# board.net
KiCad netlist of a schematic drawn in EAGLE
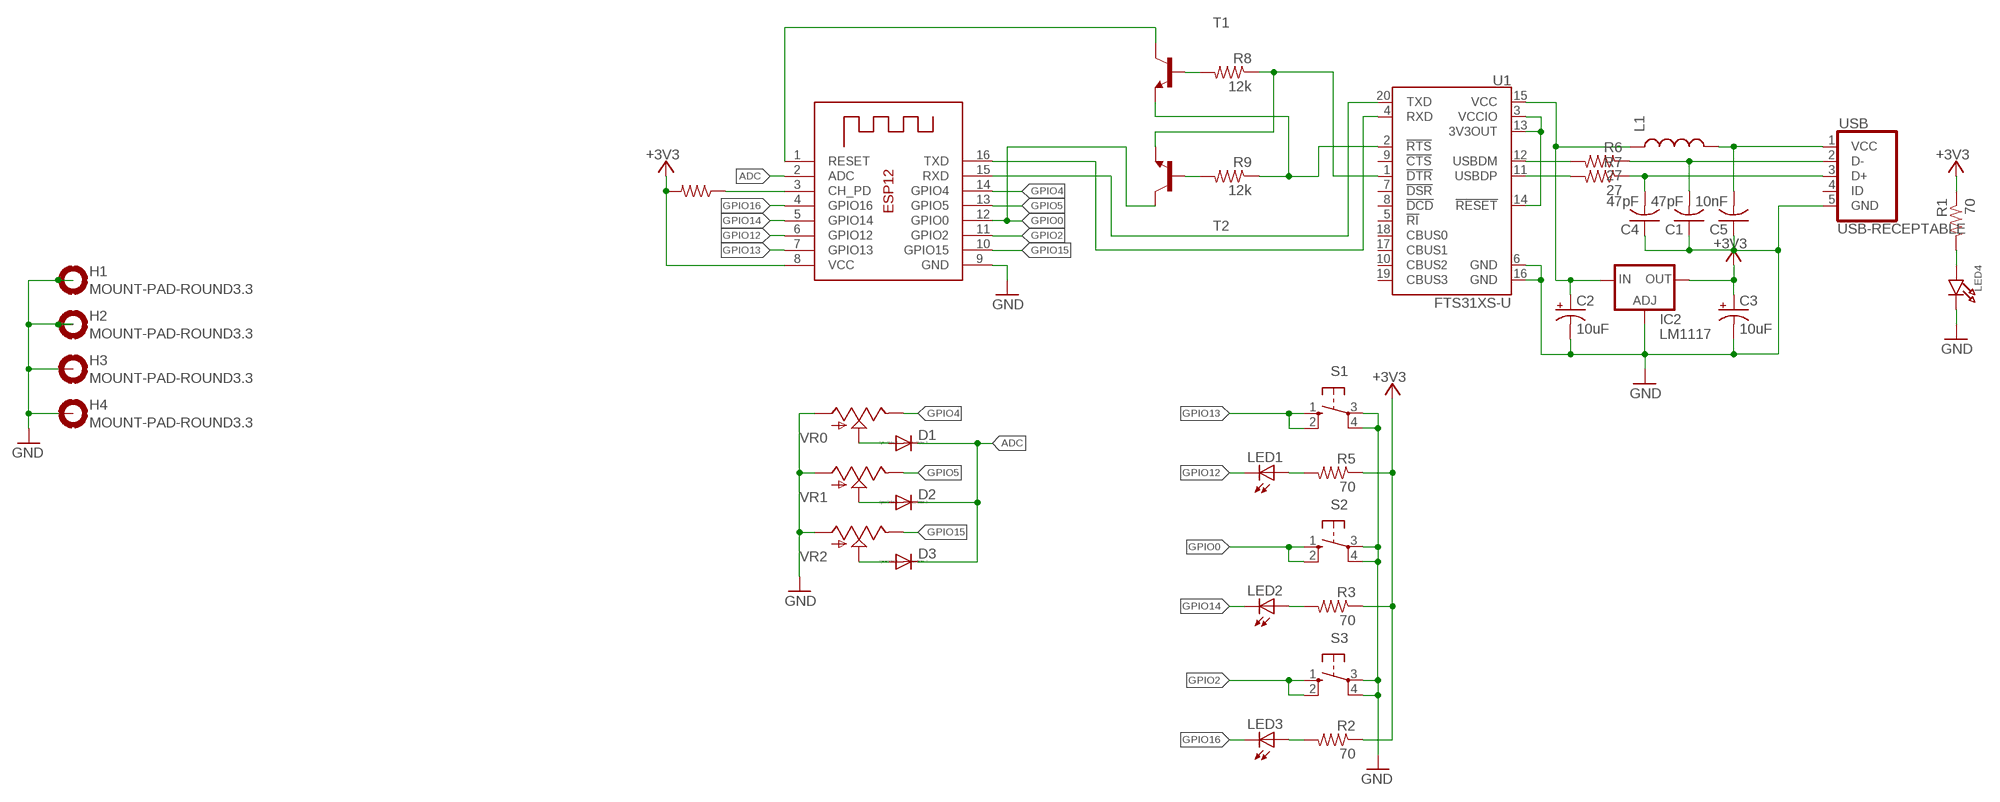
[diagram p0: schematic, sheet 1]

(export (version "E")
  (design (tool "Eeschema 10.0.6"))
  (components
    (comp (ref "C1")
      (value "47pF")
      (footprint "eagle-import:C0603")
      (libsource (lib "eagle-import") (part "C-USC0603"))
    )
    (comp (ref "C2")
      (value "10uF")
      (footprint "eagle-import:153CLV-0405")
      (libsource (lib "eagle-import") (part "CPOL-US153CLV-0405"))
    )
    (comp (ref "C3")
      (value "10uF")
      (footprint "eagle-import:153CLV-0405")
      (libsource (lib "eagle-import") (part "CPOL-US153CLV-0405"))
    )
    (comp (ref "C4")
      (value "47pF")
      (footprint "eagle-import:C0603")
      (libsource (lib "eagle-import") (part "C-USC0603"))
    )
    (comp (ref "C5")
      (value "10nF")
      (footprint "eagle-import:C0603")
      (libsource (lib "eagle-import") (part "C-USC0603"))
    )
    (comp (ref "D1")
      (value "DIODE-DO214AC")
      (footprint "eagle-import:DO214AC")
      (libsource (lib "eagle-import") (part "DIODE-DO214AC"))
    )
    (comp (ref "D2")
      (value "DIODE-DO214AC")
      (footprint "eagle-import:DO214AC")
      (libsource (lib "eagle-import") (part "DIODE-DO214AC"))
    )
    (comp (ref "D3")
      (value "DIODE-DO214AC")
      (footprint "eagle-import:DO214AC")
      (libsource (lib "eagle-import") (part "DIODE-DO214AC"))
    )
    (comp (ref "H1")
      (value "MOUNT-PAD-ROUND3.3")
      (footprint "eagle-import:3,3-PAD")
      (libsource (lib "eagle-import") (part "MOUNT-PAD-ROUND3.3"))
    )
    (comp (ref "H2")
      (value "MOUNT-PAD-ROUND3.3")
      (footprint "eagle-import:3,3-PAD")
      (libsource (lib "eagle-import") (part "MOUNT-PAD-ROUND3.3"))
    )
    (comp (ref "H3")
      (value "MOUNT-PAD-ROUND3.3")
      (footprint "eagle-import:3,3-PAD")
      (libsource (lib "eagle-import") (part "MOUNT-PAD-ROUND3.3"))
    )
    (comp (ref "H4")
      (value "MOUNT-PAD-ROUND3.3")
      (footprint "eagle-import:3,3-PAD")
      (libsource (lib "eagle-import") (part "MOUNT-PAD-ROUND3.3"))
    )
    (comp (ref "IC2")
      (value "LM1117")
      (footprint "eagle-import:DPACK")
      (libsource (lib "eagle-import") (part "LD117A?DT-TR"))
    )
    (comp (ref "L1")
      (value "INDUCTOR0805")
      (footprint "eagle-import:0805")
      (libsource (lib "eagle-import") (part "INDUCTOR0805"))
    )
    (comp (ref "LED1")
      (value "LED3MM")
      (footprint "eagle-import:LED3MM")
      (libsource (lib "eagle-import") (part "LED3MM"))
    )
    (comp (ref "LED2")
      (value "LED3MM")
      (footprint "eagle-import:LED3MM")
      (libsource (lib "eagle-import") (part "LED3MM"))
    )
    (comp (ref "LED3")
      (value "LED3MM")
      (footprint "eagle-import:LED3MM")
      (libsource (lib "eagle-import") (part "LED3MM"))
    )
    (comp (ref "LED4")
      (value "LED0805")
      (footprint "eagle-import:CHIPLED_0805")
      (libsource (lib "eagle-import") (part "LED0805"))
    )
    (comp (ref "R1")
      (value "70")
      (footprint "eagle-import:R0603")
      (libsource (lib "eagle-import") (part "R-US_R0603"))
    )
    (comp (ref "R2")
      (value "70")
      (footprint "eagle-import:R0603")
      (libsource (lib "eagle-import") (part "R-US_R0603"))
    )
    (comp (ref "R3")
      (value "70")
      (footprint "eagle-import:R0603")
      (libsource (lib "eagle-import") (part "R-US_R0603"))
    )
    (comp (ref "R4")
      (value "10k")
      (footprint "eagle-import:R0603")
      (libsource (lib "eagle-import") (part "R-US_R0603"))
    )
    (comp (ref "R5")
      (value "70")
      (footprint "eagle-import:R0603")
      (libsource (lib "eagle-import") (part "R-US_R0603"))
    )
    (comp (ref "R6")
      (value "27")
      (footprint "eagle-import:R0603")
      (libsource (lib "eagle-import") (part "R-US_R0603"))
    )
    (comp (ref "R7")
      (value "27")
      (footprint "eagle-import:R0603")
      (libsource (lib "eagle-import") (part "R-US_R0603"))
    )
    (comp (ref "R8")
      (value "12k")
      (footprint "eagle-import:R0603")
      (libsource (lib "eagle-import") (part "R-US_R0603"))
    )
    (comp (ref "R9")
      (value "12k")
      (footprint "eagle-import:R0603")
      (libsource (lib "eagle-import") (part "R-US_R0603"))
    )
    (comp (ref "S1")
      (value "10-XX")
      (footprint "eagle-import:B3F-10XX")
      (fields (field (name "MPN") "B3F-1000"))
      (libsource (lib "eagle-import") (part "10-XX"))
    )
    (comp (ref "S2")
      (value "10-XX")
      (footprint "eagle-import:B3F-10XX")
      (fields (field (name "MPN") "B3F-1000"))
      (libsource (lib "eagle-import") (part "10-XX"))
    )
    (comp (ref "S3")
      (value "10-XX")
      (footprint "eagle-import:B3F-10XX")
      (fields (field (name "MPN") "B3F-1000"))
      (libsource (lib "eagle-import") (part "10-XX"))
    )
    (comp (ref "T1")
      (value "MMBT918LT1-NPN-SOT23-BEC")
      (footprint "eagle-import:SOT23-BEC")
      (libsource (lib "eagle-import") (part "-NPN-SOT23-BECMMBT918LT1"))
    )
    (comp (ref "T2")
      (value "MMBT918LT1-NPN-SOT23-BEC")
      (footprint "eagle-import:SOT23-BEC")
      (libsource (lib "eagle-import") (part "-NPN-SOT23-BECMMBT918LT1"))
    )
    (comp (ref "U1")
      (value "FTS31XS-U")
      (footprint "eagle-import:SSOP20_L")
      (libsource (lib "eagle-import") (part "FT231XS"))
    )
    (comp (ref "USB")
      (value "USB-RECEPTABLE")
      (footprint "eagle-import:FCI-10103594-0001LF")
      (libsource (lib "eagle-import") (part "USB-RECEPTABLE"))
    )
    (comp (ref "VR0")
      (value "SLIDERPTA3043")
      (footprint "eagle-import:PTA3043-2015CPB103")
      (libsource (lib "eagle-import") (part "SLIDERPTA3043"))
    )
    (comp (ref "VR1")
      (value "SLIDERPTA3043")
      (footprint "eagle-import:PTA3043-2015CPB103")
      (libsource (lib "eagle-import") (part "SLIDERPTA3043"))
    )
    (comp (ref "VR2")
      (value "SLIDERPTA3043")
      (footprint "eagle-import:PTA3043-2015CPB103")
      (libsource (lib "eagle-import") (part "SLIDERPTA3043"))
    )
    (comp (ref "X1")
      (value "ESP-12")
      (footprint "eagle-import:ESP-12")
      (libsource (lib "eagle-import") (part "ESP-12"))
    )
  )
  (nets
    (net (code "1") (name "+3V3") (class "Default")
      (node (ref "C3") (pin "+") (pinfunction "+_+") (pintype "passive"))
      (node (ref "IC2") (pin "4") (pinfunction "OUT_4") (pintype "passive"))
      (node (ref "R1") (pin "1") (pinfunction "1_1") (pintype "passive"))
      (node (ref "R2") (pin "1") (pinfunction "1_1") (pintype "passive"))
      (node (ref "R3") (pin "1") (pinfunction "1_1") (pintype "passive"))
      (node (ref "R4") (pin "2") (pinfunction "2_2") (pintype "passive"))
      (node (ref "R5") (pin "1") (pinfunction "1_1") (pintype "passive"))
      (node (ref "X1") (pin "8") (pinfunction "VCC_8") (pintype "power_in"))
    )
    (net (code "2") (name "ADC") (class "Default")
      (node (ref "D1") (pin "C") (pinfunction "C_C") (pintype "passive"))
      (node (ref "D2") (pin "C") (pinfunction "C_C") (pintype "passive"))
      (node (ref "D3") (pin "C") (pinfunction "C_C") (pintype "passive"))
      (node (ref "X1") (pin "2") (pinfunction "ADC_2") (pintype "passive"))
    )
    (net (code "3") (name "GND") (class "Default")
      (node (ref "C1") (pin "1") (pinfunction "1_1") (pintype "passive"))
      (node (ref "C2") (pin "-") (pinfunction "-_-") (pintype "passive"))
      (node (ref "C3") (pin "-") (pinfunction "-_-") (pintype "passive"))
      (node (ref "C4") (pin "1") (pinfunction "1_1") (pintype "passive"))
      (node (ref "C5") (pin "1") (pinfunction "1_1") (pintype "passive"))
      (node (ref "H1") (pin "B3,3") (pinfunction "MOUNT_B3,3") (pintype "passive"))
      (node (ref "H2") (pin "B3,3") (pinfunction "MOUNT_B3,3") (pintype "passive"))
      (node (ref "H3") (pin "B3,3") (pinfunction "MOUNT_B3,3") (pintype "passive"))
      (node (ref "H4") (pin "B3,3") (pinfunction "MOUNT_B3,3") (pintype "passive"))
      (node (ref "IC2") (pin "1") (pinfunction "ADJ_1") (pintype "input"))
      (node (ref "LED4") (pin "C") (pinfunction "C_C") (pintype "passive"))
      (node (ref "S1") (pin "3") (pinfunction "P_3") (pintype "passive"))
      (node (ref "S1") (pin "4") (pinfunction "P1_4") (pintype "passive"))
      (node (ref "S2") (pin "3") (pinfunction "P_3") (pintype "passive"))
      (node (ref "S2") (pin "4") (pinfunction "P1_4") (pintype "passive"))
      (node (ref "S3") (pin "3") (pinfunction "P_3") (pintype "passive"))
      (node (ref "S3") (pin "4") (pinfunction "P1_4") (pintype "passive"))
      (node (ref "U1") (pin "16") (pinfunction "GND_16") (pintype "bidirectional"))
      (node (ref "U1") (pin "6") (pinfunction "GND_6") (pintype "bidirectional"))
      (node (ref "USB") (pin "5") (pinfunction "GND_5") (pintype "bidirectional"))
      (node (ref "VR0") (pin "P$1") (pinfunction "A_P$1") (pintype "passive"))
      (node (ref "VR1") (pin "P$1") (pinfunction "A_P$1") (pintype "passive"))
      (node (ref "VR2") (pin "P$1") (pinfunction "A_P$1") (pintype "passive"))
      (node (ref "X1") (pin "9") (pinfunction "GND_9") (pintype "power_in"))
    )
    (net (code "4") (name "GPIO0") (class "Default")
      (node (ref "S2") (pin "1") (pinfunction "S_1") (pintype "passive"))
      (node (ref "S2") (pin "2") (pinfunction "S1_2") (pintype "passive"))
      (node (ref "T2") (pin "C") (pinfunction "C_C") (pintype "passive"))
      (node (ref "X1") (pin "12") (pinfunction "GPIO0_12") (pintype "bidirectional"))
    )
    (net (code "5") (name "GPIO2") (class "Default")
      (node (ref "S3") (pin "1") (pinfunction "S_1") (pintype "passive"))
      (node (ref "S3") (pin "2") (pinfunction "S1_2") (pintype "passive"))
      (node (ref "X1") (pin "11") (pinfunction "GPIO2_11") (pintype "bidirectional"))
    )
    (net (code "6") (name "GPIO4") (class "Default")
      (node (ref "VR0") (pin "P$3") (pinfunction "E_P$3") (pintype "passive"))
      (node (ref "X1") (pin "14") (pinfunction "GPIO4_14") (pintype "bidirectional"))
    )
    (net (code "7") (name "GPIO5") (class "Default")
      (node (ref "VR1") (pin "P$3") (pinfunction "E_P$3") (pintype "passive"))
      (node (ref "X1") (pin "13") (pinfunction "GPIO5_13") (pintype "bidirectional"))
    )
    (net (code "8") (name "GPIO12") (class "Default")
      (node (ref "LED1") (pin "K") (pinfunction "C_K") (pintype "passive"))
      (node (ref "X1") (pin "6") (pinfunction "GPIO12_6") (pintype "bidirectional"))
    )
    (net (code "9") (name "GPIO13") (class "Default")
      (node (ref "S1") (pin "1") (pinfunction "S_1") (pintype "passive"))
      (node (ref "S1") (pin "2") (pinfunction "S1_2") (pintype "passive"))
      (node (ref "X1") (pin "7") (pinfunction "GPIO13_7") (pintype "bidirectional"))
    )
    (net (code "10") (name "GPIO14") (class "Default")
      (node (ref "LED2") (pin "K") (pinfunction "C_K") (pintype "passive"))
      (node (ref "X1") (pin "5") (pinfunction "GPIO14_5") (pintype "bidirectional"))
    )
    (net (code "11") (name "GPIO15") (class "Default")
      (node (ref "VR2") (pin "P$3") (pinfunction "E_P$3") (pintype "passive"))
      (node (ref "X1") (pin "10") (pinfunction "GPIO15_10") (pintype "bidirectional"))
    )
    (net (code "12") (name "GPIO16") (class "Default")
      (node (ref "LED3") (pin "K") (pinfunction "C_K") (pintype "passive"))
      (node (ref "X1") (pin "4") (pinfunction "GPIO16_4") (pintype "bidirectional"))
    )
    (net (code "13") (name "Net-(IC2-IN)") (class "Default")
      (node (ref "C2") (pin "+") (pinfunction "+_+") (pintype "passive"))
      (node (ref "IC2") (pin "3") (pinfunction "IN_3") (pintype "input"))
      (node (ref "L1") (pin "1") (pinfunction "1_1") (pintype "passive"))
      (node (ref "U1") (pin "15") (pinfunction "VCC_15") (pintype "bidirectional"))
    )
    (net (code "14") (name "Net-(LED1-PadA)") (class "Default")
      (node (ref "LED1") (pin "A") (pinfunction "A_A") (pintype "passive"))
      (node (ref "R5") (pin "2") (pinfunction "2_2") (pintype "passive"))
    )
    (net (code "15") (name "Net-(LED2-PadA)") (class "Default")
      (node (ref "LED2") (pin "A") (pinfunction "A_A") (pintype "passive"))
      (node (ref "R3") (pin "2") (pinfunction "2_2") (pintype "passive"))
    )
    (net (code "16") (name "Net-(LED3-PadA)") (class "Default")
      (node (ref "LED3") (pin "A") (pinfunction "A_A") (pintype "passive"))
      (node (ref "R2") (pin "2") (pinfunction "2_2") (pintype "passive"))
    )
    (net (code "17") (name "Net-(LED4-PadA)") (class "Default")
      (node (ref "LED4") (pin "A") (pinfunction "A_A") (pintype "passive"))
      (node (ref "R1") (pin "2") (pinfunction "2_2") (pintype "passive"))
    )
    (net (code "18") (name "Net-(R8-Pad2)") (class "Default")
      (node (ref "R8") (pin "2") (pinfunction "2_2") (pintype "passive"))
      (node (ref "T1") (pin "B") (pinfunction "B_B") (pintype "passive"))
    )
    (net (code "19") (name "Net-(R9-Pad2)") (class "Default")
      (node (ref "R9") (pin "2") (pinfunction "2_2") (pintype "passive"))
      (node (ref "T2") (pin "B") (pinfunction "B_B") (pintype "passive"))
    )
    (net (code "20") (name "Net-(U1-3V3OUT)") (class "Default")
      (node (ref "U1") (pin "13") (pinfunction "3V3OUT_13") (pintype "bidirectional"))
      (node (ref "U1") (pin "14") (pinfunction "~{RESET}_14") (pintype "bidirectional"))
      (node (ref "U1") (pin "3") (pinfunction "VCCIO_3") (pintype "bidirectional"))
    )
    (net (code "21") (name "Net-(U1-RXD)") (class "Default")
      (node (ref "U1") (pin "4") (pinfunction "RXD_4") (pintype "bidirectional"))
      (node (ref "X1") (pin "16") (pinfunction "TXD_16") (pintype "output"))
    )
    (net (code "22") (name "Net-(U1-TXD)") (class "Default")
      (node (ref "U1") (pin "20") (pinfunction "TXD_20") (pintype "bidirectional"))
      (node (ref "X1") (pin "15") (pinfunction "RXD_15") (pintype "input"))
    )
    (net (code "23") (name "Net-(U1-USBDM)") (class "Default")
      (node (ref "R6") (pin "2") (pinfunction "2_2") (pintype "passive"))
      (node (ref "U1") (pin "12") (pinfunction "USBDM_12") (pintype "bidirectional"))
    )
    (net (code "24") (name "Net-(U1-USBDP)") (class "Default")
      (node (ref "R7") (pin "2") (pinfunction "2_2") (pintype "passive"))
      (node (ref "U1") (pin "11") (pinfunction "USBDP_11") (pintype "bidirectional"))
    )
    (net (code "25") (name "Net-(U1-~{DTR})") (class "Default")
      (node (ref "R8") (pin "1") (pinfunction "1_1") (pintype "passive"))
      (node (ref "T2") (pin "E") (pinfunction "E_E") (pintype "passive"))
      (node (ref "U1") (pin "1") (pinfunction "~{DTR}_1") (pintype "bidirectional"))
    )
    (net (code "26") (name "Net-(U1-~{RTS})") (class "Default")
      (node (ref "R9") (pin "1") (pinfunction "1_1") (pintype "passive"))
      (node (ref "T1") (pin "E") (pinfunction "E_E") (pintype "passive"))
      (node (ref "U1") (pin "2") (pinfunction "~{RTS}_2") (pintype "bidirectional"))
    )
    (net (code "27") (name "Net-(USB-D+)") (class "Default")
      (node (ref "C4") (pin "2") (pinfunction "2_2") (pintype "passive"))
      (node (ref "R7") (pin "1") (pinfunction "1_1") (pintype "passive"))
      (node (ref "USB") (pin "3") (pinfunction "D+_3") (pintype "bidirectional"))
    )
    (net (code "28") (name "Net-(USB-D-)") (class "Default")
      (node (ref "C1") (pin "2") (pinfunction "2_2") (pintype "passive"))
      (node (ref "R6") (pin "1") (pinfunction "1_1") (pintype "passive"))
      (node (ref "USB") (pin "2") (pinfunction "D-_2") (pintype "bidirectional"))
    )
    (net (code "29") (name "Net-(USB-VCC)") (class "Default")
      (node (ref "C5") (pin "2") (pinfunction "2_2") (pintype "passive"))
      (node (ref "L1") (pin "2") (pinfunction "2_2") (pintype "passive"))
      (node (ref "USB") (pin "1") (pinfunction "VCC_1") (pintype "bidirectional"))
    )
    (net (code "30") (name "Net-(VR0-S)") (class "Default")
      (node (ref "D1") (pin "A") (pinfunction "A_A") (pintype "passive"))
      (node (ref "VR0") (pin "P$2") (pinfunction "S_P$2") (pintype "passive"))
    )
    (net (code "31") (name "Net-(VR1-S)") (class "Default")
      (node (ref "D2") (pin "A") (pinfunction "A_A") (pintype "passive"))
      (node (ref "VR1") (pin "P$2") (pinfunction "S_P$2") (pintype "passive"))
    )
    (net (code "32") (name "Net-(VR2-S)") (class "Default")
      (node (ref "D3") (pin "A") (pinfunction "A_A") (pintype "passive"))
      (node (ref "VR2") (pin "P$2") (pinfunction "S_P$2") (pintype "passive"))
    )
    (net (code "33") (name "Net-(X1-CH_PD)") (class "Default")
      (node (ref "R4") (pin "1") (pinfunction "1_1") (pintype "passive"))
      (node (ref "X1") (pin "3") (pinfunction "CH_PD_3") (pintype "input"))
    )
    (net (code "34") (name "Net-(X1-RESET)") (class "Default")
      (node (ref "T1") (pin "C") (pinfunction "C_C") (pintype "passive"))
      (node (ref "X1") (pin "1") (pinfunction "RESET_1") (pintype "input"))
    )
    (net (code "35") (name "unconnected-(U1-CBUS0-Pad18)") (class "Default")
      (node (ref "U1") (pin "18") (pinfunction "CBUS0_18") (pintype "bidirectional"))
    )
    (net (code "36") (name "unconnected-(U1-CBUS1-Pad17)") (class "Default")
      (node (ref "U1") (pin "17") (pinfunction "CBUS1_17") (pintype "bidirectional"))
    )
    (net (code "37") (name "unconnected-(U1-CBUS2-Pad10)") (class "Default")
      (node (ref "U1") (pin "10") (pinfunction "CBUS2_10") (pintype "bidirectional"))
    )
    (net (code "38") (name "unconnected-(U1-CBUS3-Pad19)") (class "Default")
      (node (ref "U1") (pin "19") (pinfunction "CBUS3_19") (pintype "bidirectional"))
    )
    (net (code "39") (name "unconnected-(U1-~{CTS}-Pad9)") (class "Default")
      (node (ref "U1") (pin "9") (pinfunction "~{CTS}_9") (pintype "bidirectional"))
    )
    (net (code "40") (name "unconnected-(U1-~{DCD}-Pad8)") (class "Default")
      (node (ref "U1") (pin "8") (pinfunction "~{DCD}_8") (pintype "bidirectional"))
    )
    (net (code "41") (name "unconnected-(U1-~{DSR}-Pad7)") (class "Default")
      (node (ref "U1") (pin "7") (pinfunction "~{DSR}_7") (pintype "bidirectional"))
    )
    (net (code "42") (name "unconnected-(U1-~{RI}-Pad5)") (class "Default")
      (node (ref "U1") (pin "5") (pinfunction "~{RI}_5") (pintype "bidirectional"))
    )
    (net (code "43") (name "unconnected-(USB-ID-Pad4)") (class "Default")
      (node (ref "USB") (pin "4") (pinfunction "ID_4") (pintype "bidirectional"))
    )
  )
)
